# attiny_lipo_alarm.net
KiCad netlist of a schematic drawn in Altium Designer
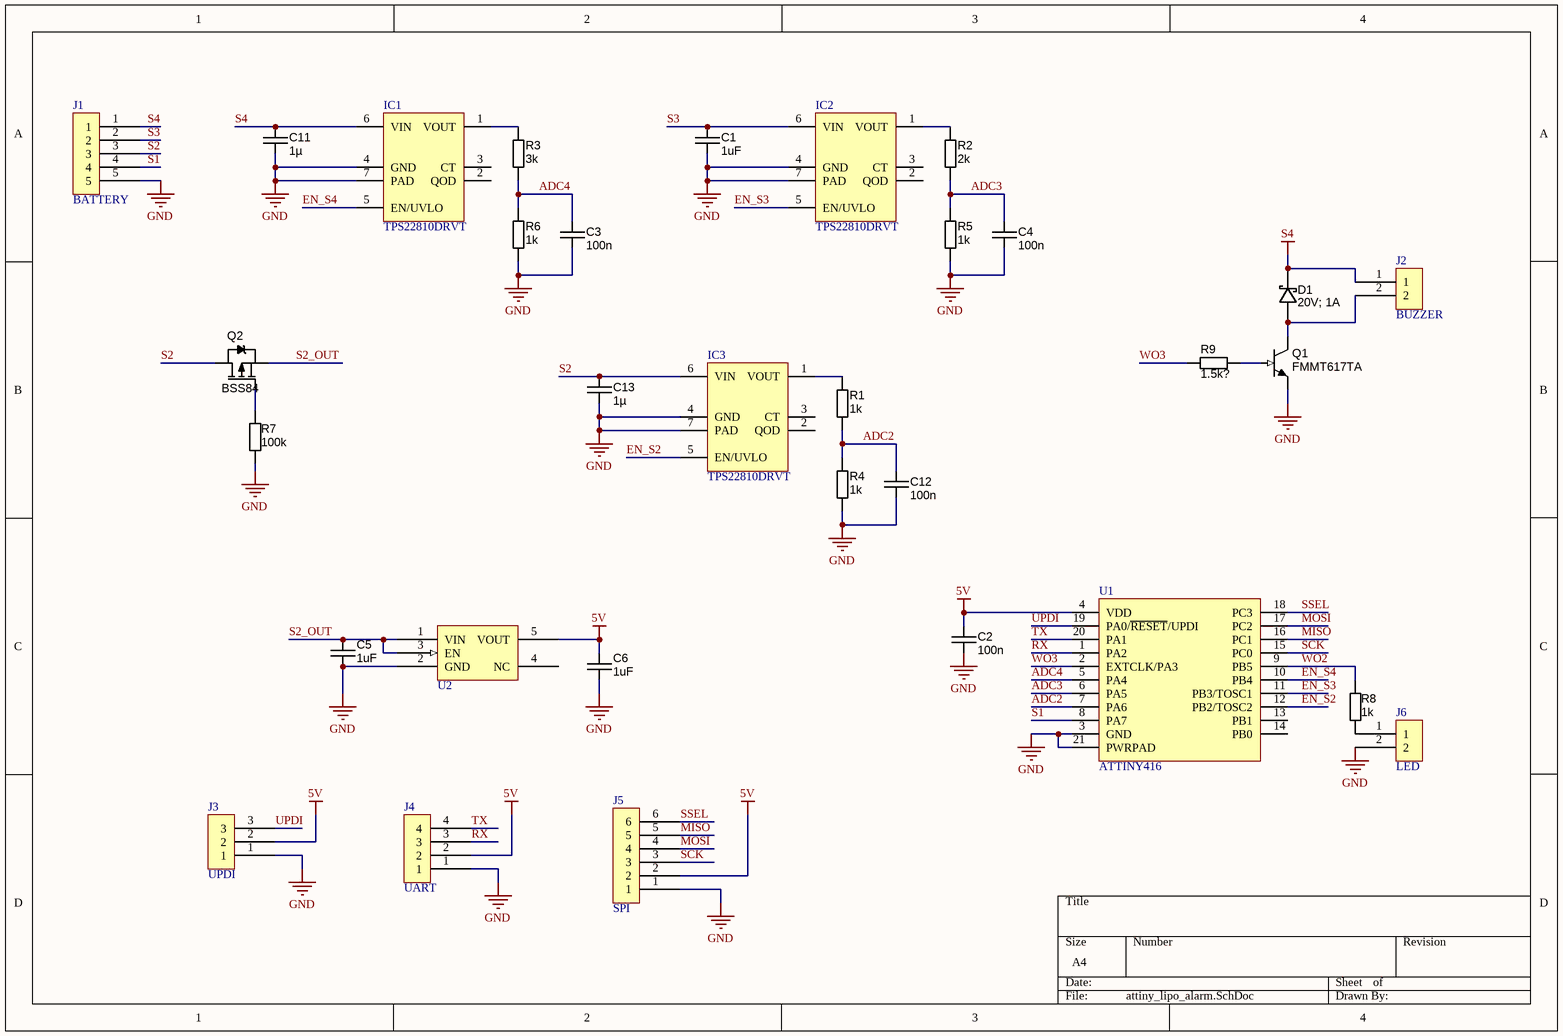
[diagram p0: attiny_lipo_alarm.SchDoc]

(export (version "E")
  (design (tool "Eeschema 10.0.6"))
  (components
    (comp (ref "C1")
      (value "1uF")
      (footprint "CAPC1608X90N")
      (description "Capacitor SMD Cer 1uF 10% 50V X7R 0603")
      (fields (field (name "TOLERANCE") "±10%"))
      (libsource (lib "PBL - Capacitors") (part "CAPC_100n_0603_X7R_50V_10%"))
    )
    (comp (ref "C2")
      (value "100n")
      (footprint "CAPC1608X90N")
      (description "Capacitor SMD Cer 100nF 10% 50V X7R 0603")
      (fields (field (name "TOLERANCE") "±10%"))
      (libsource (lib "PBL - Capacitors") (part "CAPC_100n_0603_X7R_50V_10%"))
    )
    (comp (ref "C3")
      (value "100n")
      (footprint "CAPC1608X90N")
      (description "Capacitor SMD Cer 100nF 10% 50V X7R 0603")
      (fields (field (name "TOLERANCE") "±10%"))
      (libsource (lib "PBL - Capacitors") (part "CAPC_100n_0603_X7R_50V_10%"))
    )
    (comp (ref "C4")
      (value "100n")
      (footprint "CAPC1608X90N")
      (description "Capacitor SMD Cer 100nF 10% 50V X7R 0603")
      (fields (field (name "TOLERANCE") "±10%"))
      (libsource (lib "PBL - Capacitors") (part "CAPC_100n_0603_X7R_50V_10%"))
    )
    (comp (ref "C5")
      (value "1uF")
      (footprint "CAPC1608X90N")
      (description "Capacitor SMD Cer 2.2uF 10% 10V X5R 0603")
      (fields (field (name "TOLERANCE") "±10%"))
      (libsource (lib "PBL - Capacitors") (part "CAPC_2u2_0603_10V_10%"))
    )
    (comp (ref "C6")
      (value "1uF")
      (footprint "CAPC1608X90N")
      (description "Capacitor SMD Cer 2.2uF 10% 10V X5R 0603")
      (fields (field (name "TOLERANCE") "±10%"))
      (libsource (lib "PBL - Capacitors") (part "CAPC_2u2_0603_10V_10%"))
    )
    (comp (ref "C11")
      (value "1µ")
      (footprint "CAPC1608X90N")
      (description "Capacitor SMD Cer 1uF 10% 16V X7R 0603")
      (fields (field (name "TOLERANCE") "±10%") (field (name "Comment") "approved sub OK"))
      (libsource (lib "PBL - Capacitors") (part "CAPC_1u_0603_X7R_16V_10%"))
    )
    (comp (ref "C12")
      (value "100n")
      (footprint "CAPC1608X90N")
      (description "Capacitor SMD Cer 100nF 10% 50V X7R 0603")
      (fields (field (name "TOLERANCE") "±10%"))
      (libsource (lib "PBL - Capacitors") (part "CAPC_100n_0603_X7R_50V_10%"))
    )
    (comp (ref "C13")
      (value "1µ")
      (footprint "CAPC1608X90N")
      (description "Capacitor SMD Cer 1uF 10% 16V X7R 0603")
      (fields (field (name "TOLERANCE") "±10%") (field (name "Comment") "approved sub OK"))
      (libsource (lib "PBL - Capacitors") (part "CAPC_1u_0603_X7R_16V_10%"))
    )
    (comp (ref "D1")
      (value "20V; 1A")
      (footprint "SOD123")
      (description "Diode Schottky SMD 20V 1A SOD123")
      (libsource (lib "PBL - Diodes") (part "DIODE_SCHOTTKY_40V_1A"))
    )
    (comp (ref "IC1")
      (value "TPS22810DRVT")
      (footprint "WSON-6")
      (description "Power Load Switch, 18Vin, 3A, 0.079R, WSON-6, High Side,  TPS22810, TEXAS INSTRUMENTS")
      (fields (field (name "MANUFACTURER") "Texas Instruments"))
      (libsource (lib "power") (part "TPS22810DRVT"))
    )
    (comp (ref "IC2")
      (value "TPS22810DRVT")
      (footprint "WSON-6")
      (description "Power Load Switch, 18Vin, 3A, 0.079R, WSON-6, High Side,  TPS22810, TEXAS INSTRUMENTS")
      (fields (field (name "MANUFACTURER") "Texas Instruments"))
      (libsource (lib "power") (part "TPS22810DRVT"))
    )
    (comp (ref "IC3")
      (value "TPS22810DRVT")
      (footprint "WSON-6")
      (description "Power Load Switch, 18Vin, 3A, 0.079R, WSON-6, High Side,  TPS22810, TEXAS INSTRUMENTS")
      (fields (field (name "MANUFACTURER") "Texas Instruments"))
      (libsource (lib "power") (part "TPS22810DRVT"))
    )
    (comp (ref "J1")
      (value "BATTERY")
      (footprint "PIN-HEADER-5-RA")
      (libsource (lib "connectors") (part "HEADER-5"))
    )
    (comp (ref "J2")
      (value "BUZZER")
      (footprint "PADS-2-1020")
      (libsource (lib "connectors") (part "HEADER-2"))
    )
    (comp (ref "J3")
      (value "UPDI")
      (footprint "PADS-3-1020")
      (libsource (lib "connectors") (part "HEADER-3"))
    )
    (comp (ref "J4")
      (value "UART")
      (footprint "PADS-4-1020")
      (libsource (lib "connectors") (part "HEADER-4"))
    )
    (comp (ref "J5")
      (value "SPI")
      (footprint "MICRO-MATCH-6")
      (libsource (lib "connectors") (part "HEADER-6"))
    )
    (comp (ref "J6") (value "LED") (footprint "PADS-2-1020") (libsource (lib "connectors") (part "HEADER-2")))
    (comp (ref "Q1")
      (value "~")
      (footprint "SOT23-3")
      (description "Transistor SMD NPN 15V 3A SOT-23")
      (fields (field (name "MANUFACTURER PART NUMBER 1") "FMMT617TA"))
      (libsource (lib "PBL - Transistors") (part "NPN_FMMT617TA"))
    )
    (comp (ref "Q2")
      (value "BSS84")
      (footprint "SOT23-3")
      (description "MOSFET SMD P-CH 50V 130mA SOT23-3")
      (libsource (lib "PBL - Transistors") (part "MOSFET_BSS84"))
    )
    (comp (ref "R1")
      (value "1k")
      (footprint "RESC1608X55N")
      (description "Resistor SMD chip 1k Ohm 0.1W 5% 0603")
      (fields (field (name "TOLERANCE") "±5%"))
      (libsource (lib "PBL - Resistors") (part "RES_1K_0603_5%"))
    )
    (comp (ref "R2")
      (value "2k")
      (footprint "RESC1608X55N")
      (description "Resistor SMD chip 1k Ohm 0.1W 5% 0603")
      (fields (field (name "TOLERANCE") "±5%"))
      (libsource (lib "PBL - Resistors") (part "RES_1K_0603_5%"))
    )
    (comp (ref "R3")
      (value "3k")
      (footprint "RESC1608X55N")
      (description "Resistor SMD chip 1k Ohm 0.1W 5% 0603")
      (fields (field (name "TOLERANCE") "±5%"))
      (libsource (lib "PBL - Resistors") (part "RES_1K_0603_5%"))
    )
    (comp (ref "R4")
      (value "1k")
      (footprint "RESC1608X55N")
      (description "Resistor SMD chip 1k Ohm 0.1W 5% 0603")
      (fields (field (name "TOLERANCE") "±5%"))
      (libsource (lib "PBL - Resistors") (part "RES_1K_0603_5%"))
    )
    (comp (ref "R5")
      (value "1k")
      (footprint "RESC1608X55N")
      (description "Resistor SMD chip 1k Ohm 0.1W 5% 0603")
      (fields (field (name "TOLERANCE") "±5%"))
      (libsource (lib "PBL - Resistors") (part "RES_1K_0603_5%"))
    )
    (comp (ref "R6")
      (value "1k")
      (footprint "RESC1608X55N")
      (description "Resistor SMD chip 1k Ohm 0.1W 5% 0603")
      (fields (field (name "TOLERANCE") "±5%"))
      (libsource (lib "PBL - Resistors") (part "RES_1K_0603_5%"))
    )
    (comp (ref "R7")
      (value "100k")
      (footprint "RESC1608X55N")
      (description "Resistor SMD chip 1k Ohm 0.1W 5% 0603")
      (fields (field (name "TOLERANCE") "±5%"))
      (libsource (lib "") (part "RES_1K_0603_5%_1"))
    )
    (comp (ref "R8")
      (value "1k")
      (footprint "RESC1608X55N")
      (description "Resistor SMD chip 1k Ohm 0.1W 5% 0603")
      (fields (field (name "TOLERANCE") "±5%"))
      (libsource (lib "PBL - Resistors") (part "RES_1K_0603_5%"))
    )
    (comp (ref "R9")
      (value "1.5k?")
      (footprint "RESC1608X55N")
      (description "Resistor SMD chip 1k Ohm 0.1W 5% 0603")
      (fields (field (name "TOLERANCE") "±5%"))
      (libsource (lib "") (part "RES_1K_0603_5%_1"))
    )
    (comp (ref "U1")
      (value "ATTINY416")
      (footprint "QFN40P300X300X90_HS-21M")
      (libsource (lib "atmel") (part "ATTINY416"))
    )
    (comp (ref "U2")
      (value "LDO-SOT23-5")
      (footprint "SOT23-5")
      (libsource (lib "power") (part "LDO-SOT23-5"))
    )
  )
  (nets
    (net (code "1") (name "/ADC2") (class "Default")
      (node (ref "C12") (pin "1") (pintype "passive"))
      (node (ref "R1") (pin "2") (pinfunction "2_2") (pintype "passive"))
      (node (ref "R4") (pin "1") (pinfunction "1_1") (pintype "passive"))
      (node (ref "U1") (pin "7") (pinfunction "PA6_7") (pintype "passive"))
    )
    (net (code "2") (name "/ADC3") (class "Default")
      (node (ref "C4") (pin "1") (pintype "passive"))
      (node (ref "R2") (pin "2") (pinfunction "2_2") (pintype "passive"))
      (node (ref "R5") (pin "1") (pinfunction "1_1") (pintype "passive"))
      (node (ref "U1") (pin "6") (pinfunction "PA5_6") (pintype "passive"))
    )
    (net (code "3") (name "/ADC4") (class "Default")
      (node (ref "C3") (pin "1") (pintype "passive"))
      (node (ref "R3") (pin "2") (pinfunction "2_2") (pintype "passive"))
      (node (ref "R6") (pin "1") (pinfunction "1_1") (pintype "passive"))
      (node (ref "U1") (pin "5") (pinfunction "PA4_5") (pintype "passive"))
    )
    (net (code "4") (name "/EN_S2") (class "Default")
      (node (ref "IC3") (pin "5") (pinfunction "EN/UVLO_5") (pintype "passive"))
      (node (ref "U1") (pin "12") (pinfunction "PB2/TOSC2_12") (pintype "passive"))
    )
    (net (code "5") (name "/EN_S3") (class "Default")
      (node (ref "IC2") (pin "5") (pinfunction "EN/UVLO_5") (pintype "passive"))
      (node (ref "U1") (pin "11") (pinfunction "PB3/TOSC1_11") (pintype "passive"))
    )
    (net (code "6") (name "/EN_S4") (class "Default")
      (node (ref "IC1") (pin "5") (pinfunction "EN/UVLO_5") (pintype "passive"))
      (node (ref "U1") (pin "10") (pinfunction "PB4_10") (pintype "passive"))
    )
    (net (code "7") (name "/MISO") (class "Default")
      (node (ref "J5") (pin "5") (pinfunction "5_5") (pintype "passive"))
      (node (ref "U1") (pin "16") (pinfunction "PC1_16") (pintype "passive"))
    )
    (net (code "8") (name "/MOSI") (class "Default")
      (node (ref "J5") (pin "4") (pinfunction "4_4") (pintype "passive"))
      (node (ref "U1") (pin "17") (pinfunction "PC2_17") (pintype "passive"))
    )
    (net (code "9") (name "/RX") (class "Default")
      (node (ref "J4") (pin "3") (pinfunction "3_3") (pintype "passive"))
      (node (ref "U1") (pin "1") (pinfunction "PA2_1") (pintype "passive"))
    )
    (net (code "10") (name "/S1") (class "Default")
      (node (ref "J1") (pin "4") (pinfunction "4_4") (pintype "passive"))
      (node (ref "U1") (pin "8") (pinfunction "PA7_8") (pintype "passive"))
    )
    (net (code "11") (name "/S2") (class "Default")
      (node (ref "C13") (pin "1") (pintype "passive"))
      (node (ref "IC3") (pin "6") (pinfunction "VIN_6") (pintype "passive"))
      (node (ref "J1") (pin "3") (pinfunction "3_3") (pintype "passive"))
      (node (ref "Q2") (pin "3") (pinfunction "D_3") (pintype "passive"))
    )
    (net (code "12") (name "/S2_OUT") (class "Default")
      (node (ref "C5") (pin "1") (pintype "passive"))
      (node (ref "Q2") (pin "2") (pinfunction "S_2") (pintype "passive"))
      (node (ref "U2") (pin "1") (pinfunction "VIN_1") (pintype "power_in"))
      (node (ref "U2") (pin "3") (pinfunction "EN_3") (pintype "input"))
    )
    (net (code "13") (name "/S3") (class "Default")
      (node (ref "C1") (pin "1") (pintype "passive"))
      (node (ref "IC2") (pin "6") (pinfunction "VIN_6") (pintype "passive"))
      (node (ref "J1") (pin "2") (pinfunction "2_2") (pintype "passive"))
    )
    (net (code "14") (name "/SCK") (class "Default")
      (node (ref "J5") (pin "3") (pinfunction "3_3") (pintype "passive"))
      (node (ref "U1") (pin "15") (pinfunction "PC0_15") (pintype "passive"))
    )
    (net (code "15") (name "/SSEL") (class "Default")
      (node (ref "J5") (pin "6") (pinfunction "6_6") (pintype "passive"))
      (node (ref "U1") (pin "18") (pinfunction "PC3_18") (pintype "passive"))
    )
    (net (code "16") (name "/TX") (class "Default")
      (node (ref "J4") (pin "4") (pinfunction "4_4") (pintype "passive"))
      (node (ref "U1") (pin "20") (pinfunction "PA1_20") (pintype "passive"))
    )
    (net (code "17") (name "/UPDI") (class "Default")
      (node (ref "J3") (pin "3") (pinfunction "3_3") (pintype "passive"))
      (node (ref "U1") (pin "19") (pinfunction "PA0/~{RESET}/UPDI_19") (pintype "passive"))
    )
    (net (code "18") (name "/WO2") (class "Default")
      (node (ref "R8") (pin "1") (pinfunction "1_1") (pintype "passive"))
      (node (ref "U1") (pin "9") (pinfunction "PB5_9") (pintype "passive"))
    )
    (net (code "19") (name "/WO3") (class "Default")
      (node (ref "R9") (pin "1") (pinfunction "1_1") (pintype "passive"))
      (node (ref "U1") (pin "2") (pinfunction "EXTCLK/PA3_2") (pintype "passive"))
    )
    (net (code "20") (name "5V") (class "Default")
      (node (ref "C2") (pin "1") (pintype "passive"))
      (node (ref "C6") (pin "1") (pintype "passive"))
      (node (ref "J3") (pin "2") (pinfunction "2_2") (pintype "passive"))
      (node (ref "J4") (pin "2") (pinfunction "2_2") (pintype "passive"))
      (node (ref "J5") (pin "2") (pinfunction "2_2") (pintype "passive"))
      (node (ref "U1") (pin "4") (pinfunction "VDD_4") (pintype "passive"))
      (node (ref "U2") (pin "5") (pinfunction "VOUT_5") (pintype "passive"))
    )
    (net (code "21") (name "GND") (class "Default")
      (node (ref "C1") (pin "2") (pintype "passive"))
      (node (ref "C11") (pin "2") (pintype "passive"))
      (node (ref "C12") (pin "2") (pintype "passive"))
      (node (ref "C13") (pin "2") (pintype "passive"))
      (node (ref "C2") (pin "2") (pintype "passive"))
      (node (ref "C3") (pin "2") (pintype "passive"))
      (node (ref "C4") (pin "2") (pintype "passive"))
      (node (ref "C5") (pin "2") (pintype "passive"))
      (node (ref "C6") (pin "2") (pintype "passive"))
      (node (ref "IC1") (pin "4") (pinfunction "GND_4") (pintype "passive"))
      (node (ref "IC1") (pin "7") (pinfunction "PAD_7") (pintype "passive"))
      (node (ref "IC2") (pin "4") (pinfunction "GND_4") (pintype "passive"))
      (node (ref "IC2") (pin "7") (pinfunction "PAD_7") (pintype "passive"))
      (node (ref "IC3") (pin "4") (pinfunction "GND_4") (pintype "passive"))
      (node (ref "IC3") (pin "7") (pinfunction "PAD_7") (pintype "passive"))
      (node (ref "J1") (pin "5") (pinfunction "5_5") (pintype "passive"))
      (node (ref "J3") (pin "1") (pinfunction "1_1") (pintype "passive"))
      (node (ref "J4") (pin "1") (pinfunction "1_1") (pintype "passive"))
      (node (ref "J5") (pin "1") (pinfunction "1_1") (pintype "passive"))
      (node (ref "J6") (pin "2") (pinfunction "2_2") (pintype "passive"))
      (node (ref "Q1") (pin "2") (pinfunction "E_2") (pintype "passive"))
      (node (ref "R4") (pin "2") (pinfunction "2_2") (pintype "passive"))
      (node (ref "R5") (pin "2") (pinfunction "2_2") (pintype "passive"))
      (node (ref "R6") (pin "2") (pinfunction "2_2") (pintype "passive"))
      (node (ref "R7") (pin "1") (pinfunction "1_1") (pintype "passive"))
      (node (ref "U1") (pin "21") (pinfunction "PWRPAD_21") (pintype "passive"))
      (node (ref "U1") (pin "3") (pinfunction "GND_3") (pintype "passive"))
      (node (ref "U2") (pin "2") (pinfunction "GND_2") (pintype "power_in"))
    )
    (net (code "22") (name "Net-(IC1-VOUT)") (class "Default")
      (node (ref "IC1") (pin "1") (pinfunction "VOUT_1") (pintype "passive"))
      (node (ref "R3") (pin "1") (pinfunction "1_1") (pintype "passive"))
    )
    (net (code "23") (name "Net-(IC2-VOUT)") (class "Default")
      (node (ref "IC2") (pin "1") (pinfunction "VOUT_1") (pintype "passive"))
      (node (ref "R2") (pin "1") (pinfunction "1_1") (pintype "passive"))
    )
    (net (code "24") (name "Net-(IC3-VOUT)") (class "Default")
      (node (ref "IC3") (pin "1") (pinfunction "VOUT_1") (pintype "passive"))
      (node (ref "R1") (pin "1") (pinfunction "1_1") (pintype "passive"))
    )
    (net (code "25") (name "Net-(J6-Pad1)") (class "Default")
      (node (ref "J6") (pin "1") (pinfunction "1_1") (pintype "passive"))
      (node (ref "R8") (pin "2") (pinfunction "2_2") (pintype "passive"))
    )
    (net (code "26") (name "Net-(Q1-B)") (class "Default")
      (node (ref "Q1") (pin "1") (pinfunction "B_1") (pintype "input"))
      (node (ref "R9") (pin "2") (pinfunction "2_2") (pintype "passive"))
    )
    (net (code "27") (name "Net-(Q1-C)") (class "Default")
      (node (ref "D1") (pin "A") (pinfunction "A_A") (pintype "passive"))
      (node (ref "J2") (pin "2") (pinfunction "2_2") (pintype "passive"))
      (node (ref "Q1") (pin "3") (pinfunction "C_3") (pintype "passive"))
    )
    (net (code "28") (name "Net-(Q2-G)") (class "Default")
      (node (ref "Q2") (pin "1") (pinfunction "G_1") (pintype "passive"))
      (node (ref "R7") (pin "2") (pinfunction "2_2") (pintype "passive"))
    )
    (net (code "29") (name "S4") (class "Default")
      (node (ref "C11") (pin "1") (pintype "passive"))
      (node (ref "D1") (pin "K") (pinfunction "K_K") (pintype "passive"))
      (node (ref "IC1") (pin "6") (pinfunction "VIN_6") (pintype "passive"))
      (node (ref "J1") (pin "1") (pinfunction "1_1") (pintype "passive"))
      (node (ref "J2") (pin "1") (pinfunction "1_1") (pintype "passive"))
    )
    (net (code "30") (name "unconnected-(IC1-CT-Pad3)") (class "Default")
      (node (ref "IC1") (pin "3") (pinfunction "CT_3") (pintype "passive"))
    )
    (net (code "31") (name "unconnected-(IC1-QOD-Pad2)") (class "Default")
      (node (ref "IC1") (pin "2") (pinfunction "QOD_2") (pintype "passive"))
    )
    (net (code "32") (name "unconnected-(IC2-CT-Pad3)") (class "Default")
      (node (ref "IC2") (pin "3") (pinfunction "CT_3") (pintype "passive"))
    )
    (net (code "33") (name "unconnected-(IC2-QOD-Pad2)") (class "Default")
      (node (ref "IC2") (pin "2") (pinfunction "QOD_2") (pintype "passive"))
    )
    (net (code "34") (name "unconnected-(IC3-CT-Pad3)") (class "Default")
      (node (ref "IC3") (pin "3") (pinfunction "CT_3") (pintype "passive"))
    )
    (net (code "35") (name "unconnected-(IC3-QOD-Pad2)") (class "Default")
      (node (ref "IC3") (pin "2") (pinfunction "QOD_2") (pintype "passive"))
    )
    (net (code "36") (name "unconnected-(U1-PB0-Pad14)") (class "Default")
      (node (ref "U1") (pin "14") (pinfunction "PB0_14") (pintype "passive"))
    )
    (net (code "37") (name "unconnected-(U1-PB1-Pad13)") (class "Default")
      (node (ref "U1") (pin "13") (pinfunction "PB1_13") (pintype "passive"))
    )
    (net (code "38") (name "unconnected-(U2-NC-Pad4)") (class "Default")
      (node (ref "U2") (pin "4") (pinfunction "NC_4") (pintype "power_in"))
    )
  )
)
